# MicroSdCard.net
KiCad netlist of a schematic drawn in Altium Designer
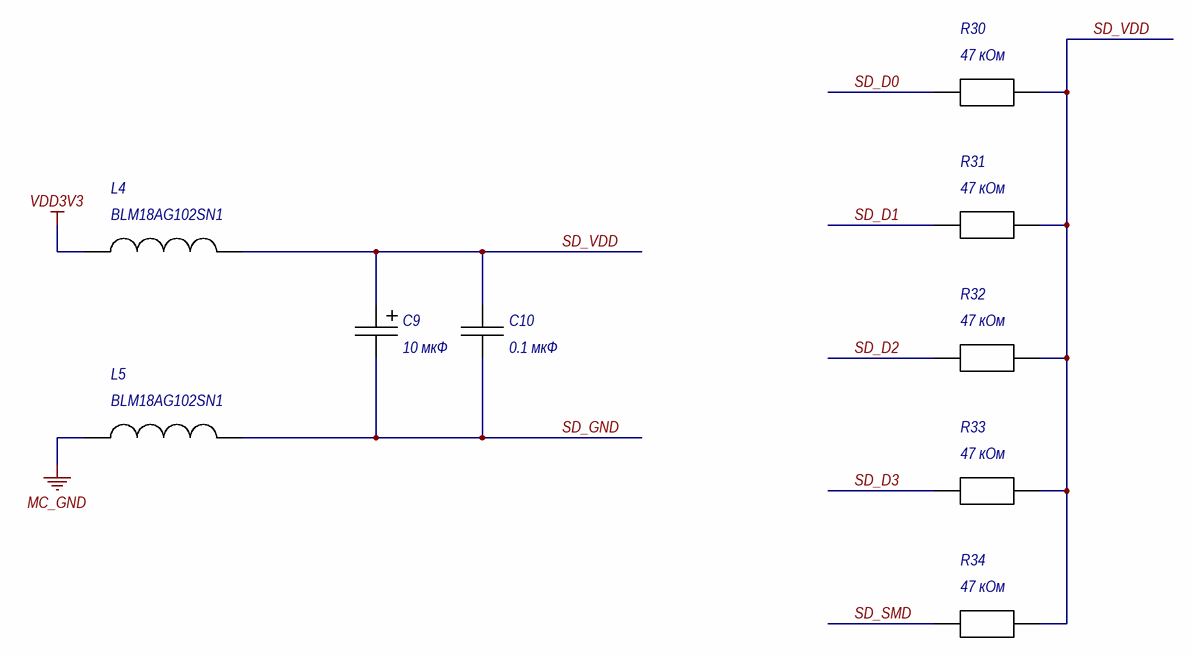
[diagram p0: MicroSdCard.SchDoc]

(export (version "E")
  (design (tool "Eeschema 10.0.6"))
  (components
    (comp (ref "C9")
      (value "10 мкФ")
      (footprint "C TAN_A")
      (description "SMD Tantalium Capacitor A")
      (libsource (lib "my_lib") (part "CAP TAN_A"))
    )
    (comp (ref "C10")
      (value "0.1 мкФ")
      (footprint "C 0805")
      (description "SMD Capacitor 0805")
      (fields
        (field (name "TOLERANCE") "/Укажите допуск в процентах/")
        (field (name "MANUFACTURER") "/Укажите компанию-производителя/")
      )
      (libsource (lib "my_lib") (part "CAP 0805"))
    )
    (comp (ref "L4")
      (value "BLM18AG102SN1")
      (footprint "FB 0603")
      (libsource (lib "my_lib") (part "BLM18AG102SN1"))
    )
    (comp (ref "L5")
      (value "BLM18AG102SN1")
      (footprint "FB 0603")
      (libsource (lib "my_lib") (part "BLM18AG102SN1"))
    )
    (comp (ref "R30") (value "47 кОм") (footprint "RES 0402") (libsource (lib "my_lib") (part "RES 0402")))
    (comp (ref "R31") (value "47 кОм") (footprint "RES 0402") (libsource (lib "my_lib") (part "RES 0402")))
    (comp (ref "R32") (value "47 кОм") (footprint "RES 0402") (libsource (lib "my_lib") (part "RES 0402")))
    (comp (ref "R33") (value "47 кОм") (footprint "RES 0402") (libsource (lib "my_lib") (part "RES 0402")))
    (comp (ref "R34") (value "47 кОм") (footprint "RES 0402") (libsource (lib "my_lib") (part "RES 0402")))
  )
  (nets
    (net (code "1") (name "/SD_D0") (class "Default")
      (node (ref "R30") (pin "2") (pinfunction "2_2") (pintype "passive"))
    )
    (net (code "2") (name "/SD_D1") (class "Default")
      (node (ref "R31") (pin "2") (pinfunction "2_2") (pintype "passive"))
    )
    (net (code "3") (name "/SD_D2") (class "Default")
      (node (ref "R32") (pin "2") (pinfunction "2_2") (pintype "passive"))
    )
    (net (code "4") (name "/SD_D3") (class "Default")
      (node (ref "R33") (pin "2") (pinfunction "2_2") (pintype "passive"))
    )
    (net (code "5") (name "/SD_GND") (class "Default")
      (node (ref "C10") (pin "2") (pinfunction "2_2") (pintype "passive"))
      (node (ref "C9") (pin "2") (pinfunction "2_2") (pintype "passive"))
      (node (ref "L5") (pin "2") (pinfunction "2_2") (pintype "passive"))
    )
    (net (code "6") (name "/SD_SMD") (class "Default")
      (node (ref "R34") (pin "2") (pinfunction "2_2") (pintype "passive"))
    )
    (net (code "7") (name "/SD_VDD") (class "Default")
      (node (ref "C10") (pin "1") (pinfunction "1_1") (pintype "passive"))
      (node (ref "C9") (pin "1") (pinfunction "1_1") (pintype "passive"))
      (node (ref "L4") (pin "2") (pinfunction "2_2") (pintype "passive"))
      (node (ref "R30") (pin "1") (pinfunction "1_1") (pintype "passive"))
      (node (ref "R31") (pin "1") (pinfunction "1_1") (pintype "passive"))
      (node (ref "R32") (pin "1") (pinfunction "1_1") (pintype "passive"))
      (node (ref "R33") (pin "1") (pinfunction "1_1") (pintype "passive"))
      (node (ref "R34") (pin "1") (pinfunction "1_1") (pintype "passive"))
    )
    (net (code "8") (name "MC_GND") (class "Default")
      (node (ref "L5") (pin "1") (pinfunction "1_1") (pintype "passive"))
    )
    (net (code "9") (name "VDD3V3") (class "Default")
      (node (ref "L4") (pin "1") (pinfunction "1_1") (pintype "passive"))
    )
  )
)
